# doantk.net
KiCad netlist of a schematic drawn in Altium Designer
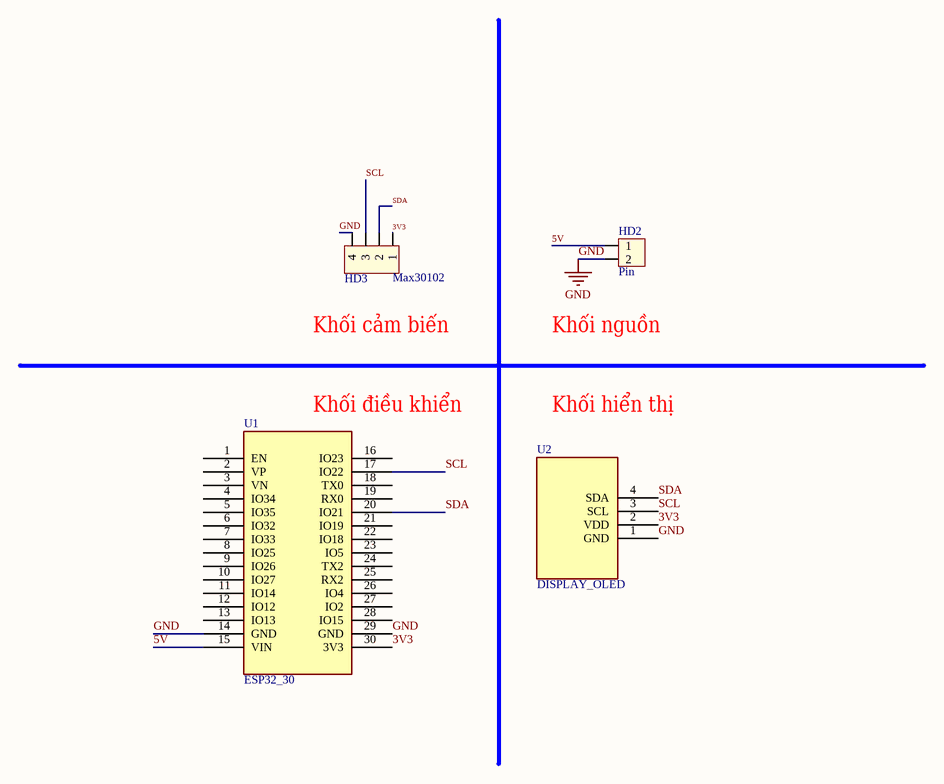
[diagram p0: doantk.SchDoc]

(export (version "E")
  (design (tool "Eeschema 10.0.6"))
  (components
    (comp (ref "HD2")
      (value "Pin")
      (footprint "HED2")
      (description "Header 2 (Green)")
      (libsource (lib "syhaunguyen") (part "Hed2"))
    )
    (comp (ref "HD3")
      (value "Max30102")
      (footprint "HED4")
      (description "Header 4 (Green)")
      (libsource (lib "syhaunguyen") (part "Hed4"))
    )
    (comp (ref "U1")
      (value "ESP32_30")
      (footprint "ESP32_30")
      (description "Microcontoller Board 30 Pins Wifi 2.4GHz BLE 4.2 ESP32-WROOM-32D")
      (libsource (lib "Espressif Microcontrollers") (part "ESP32_30"))
    )
    (comp (ref "U2")
      (value "DISPLAY_OLED")
      (footprint "DISPLAY_OLED")
      (description "Display Oled 128x64 0.96\" I2C.")
      (libsource (lib "Displays") (part "DISPLAY_OLED"))
    )
  )
  (nets
    (net (code "1") (name "/3V3") (class "Default")
      (node (ref "HD3") (pin "1") (pinfunction "1_1") (pintype "passive"))
      (node (ref "U1") (pin "30") (pinfunction "3V3_30") (pintype "passive"))
      (node (ref "U2") (pin "2") (pinfunction "VDD_2") (pintype "tri_state"))
    )
    (net (code "2") (name "/5V") (class "Default")
      (node (ref "HD2") (pin "1") (pinfunction "1_1") (pintype "passive"))
      (node (ref "U1") (pin "15") (pinfunction "VIN_15") (pintype "passive"))
    )
    (net (code "3") (name "/SCL") (class "Default")
      (node (ref "HD3") (pin "3") (pinfunction "3_3") (pintype "passive"))
      (node (ref "U1") (pin "17") (pinfunction "IO22_17") (pintype "passive"))
      (node (ref "U2") (pin "3") (pinfunction "SCL_3") (pintype "tri_state"))
    )
    (net (code "4") (name "/SDA") (class "Default")
      (node (ref "HD3") (pin "2") (pinfunction "2_2") (pintype "passive"))
      (node (ref "U1") (pin "20") (pinfunction "IO21_20") (pintype "passive"))
      (node (ref "U2") (pin "4") (pinfunction "SDA_4") (pintype "tri_state"))
    )
    (net (code "5") (name "GND") (class "Default")
      (node (ref "HD2") (pin "2") (pinfunction "2_2") (pintype "passive"))
      (node (ref "HD3") (pin "4") (pinfunction "4_4") (pintype "passive"))
      (node (ref "U1") (pin "14") (pinfunction "GND_14") (pintype "passive"))
      (node (ref "U1") (pin "29") (pinfunction "GND_29") (pintype "passive"))
      (node (ref "U2") (pin "1") (pinfunction "GND_1") (pintype "tri_state"))
    )
    (net (code "6") (name "unconnected-(U1-EN-Pad1)") (class "Default")
      (node (ref "U1") (pin "1") (pinfunction "EN_1") (pintype "passive"))
    )
    (net (code "7") (name "unconnected-(U1-IO2-Pad27)") (class "Default")
      (node (ref "U1") (pin "27") (pinfunction "IO2_27") (pintype "passive"))
    )
    (net (code "8") (name "unconnected-(U1-IO4-Pad26)") (class "Default")
      (node (ref "U1") (pin "26") (pinfunction "IO4_26") (pintype "passive"))
    )
    (net (code "9") (name "unconnected-(U1-IO5-Pad23)") (class "Default")
      (node (ref "U1") (pin "23") (pinfunction "IO5_23") (pintype "passive"))
    )
    (net (code "10") (name "unconnected-(U1-IO12-Pad12)") (class "Default")
      (node (ref "U1") (pin "12") (pinfunction "IO12_12") (pintype "passive"))
    )
    (net (code "11") (name "unconnected-(U1-IO13-Pad13)") (class "Default")
      (node (ref "U1") (pin "13") (pinfunction "IO13_13") (pintype "passive"))
    )
    (net (code "12") (name "unconnected-(U1-IO14-Pad11)") (class "Default")
      (node (ref "U1") (pin "11") (pinfunction "IO14_11") (pintype "passive"))
    )
    (net (code "13") (name "unconnected-(U1-IO15-Pad28)") (class "Default")
      (node (ref "U1") (pin "28") (pinfunction "IO15_28") (pintype "passive"))
    )
    (net (code "14") (name "unconnected-(U1-IO18-Pad22)") (class "Default")
      (node (ref "U1") (pin "22") (pinfunction "IO18_22") (pintype "passive"))
    )
    (net (code "15") (name "unconnected-(U1-IO19-Pad21)") (class "Default")
      (node (ref "U1") (pin "21") (pinfunction "IO19_21") (pintype "passive"))
    )
    (net (code "16") (name "unconnected-(U1-IO23-Pad16)") (class "Default")
      (node (ref "U1") (pin "16") (pinfunction "IO23_16") (pintype "passive"))
    )
    (net (code "17") (name "unconnected-(U1-IO25-Pad8)") (class "Default")
      (node (ref "U1") (pin "8") (pinfunction "IO25_8") (pintype "passive"))
    )
    (net (code "18") (name "unconnected-(U1-IO26-Pad9)") (class "Default")
      (node (ref "U1") (pin "9") (pinfunction "IO26_9") (pintype "passive"))
    )
    (net (code "19") (name "unconnected-(U1-IO27-Pad10)") (class "Default")
      (node (ref "U1") (pin "10") (pinfunction "IO27_10") (pintype "passive"))
    )
    (net (code "20") (name "unconnected-(U1-IO32-Pad6)") (class "Default")
      (node (ref "U1") (pin "6") (pinfunction "IO32_6") (pintype "passive"))
    )
    (net (code "21") (name "unconnected-(U1-IO33-Pad7)") (class "Default")
      (node (ref "U1") (pin "7") (pinfunction "IO33_7") (pintype "passive"))
    )
    (net (code "22") (name "unconnected-(U1-IO34-Pad4)") (class "Default")
      (node (ref "U1") (pin "4") (pinfunction "IO34_4") (pintype "passive"))
    )
    (net (code "23") (name "unconnected-(U1-IO35-Pad5)") (class "Default")
      (node (ref "U1") (pin "5") (pinfunction "IO35_5") (pintype "passive"))
    )
    (net (code "24") (name "unconnected-(U1-RX0-Pad19)") (class "Default")
      (node (ref "U1") (pin "19") (pinfunction "RX0_19") (pintype "passive"))
    )
    (net (code "25") (name "unconnected-(U1-RX2-Pad25)") (class "Default")
      (node (ref "U1") (pin "25") (pinfunction "RX2_25") (pintype "passive"))
    )
    (net (code "26") (name "unconnected-(U1-TX0-Pad18)") (class "Default")
      (node (ref "U1") (pin "18") (pinfunction "TX0_18") (pintype "passive"))
    )
    (net (code "27") (name "unconnected-(U1-TX2-Pad24)") (class "Default")
      (node (ref "U1") (pin "24") (pinfunction "TX2_24") (pintype "passive"))
    )
    (net (code "28") (name "unconnected-(U1-VN-Pad3)") (class "Default")
      (node (ref "U1") (pin "3") (pinfunction "VN_3") (pintype "passive"))
    )
    (net (code "29") (name "unconnected-(U1-VP-Pad2)") (class "Default")
      (node (ref "U1") (pin "2") (pinfunction "VP_2") (pintype "passive"))
    )
  )
)
